# IMArduino-v1.net
KiCad netlist of a schematic drawn in EAGLE
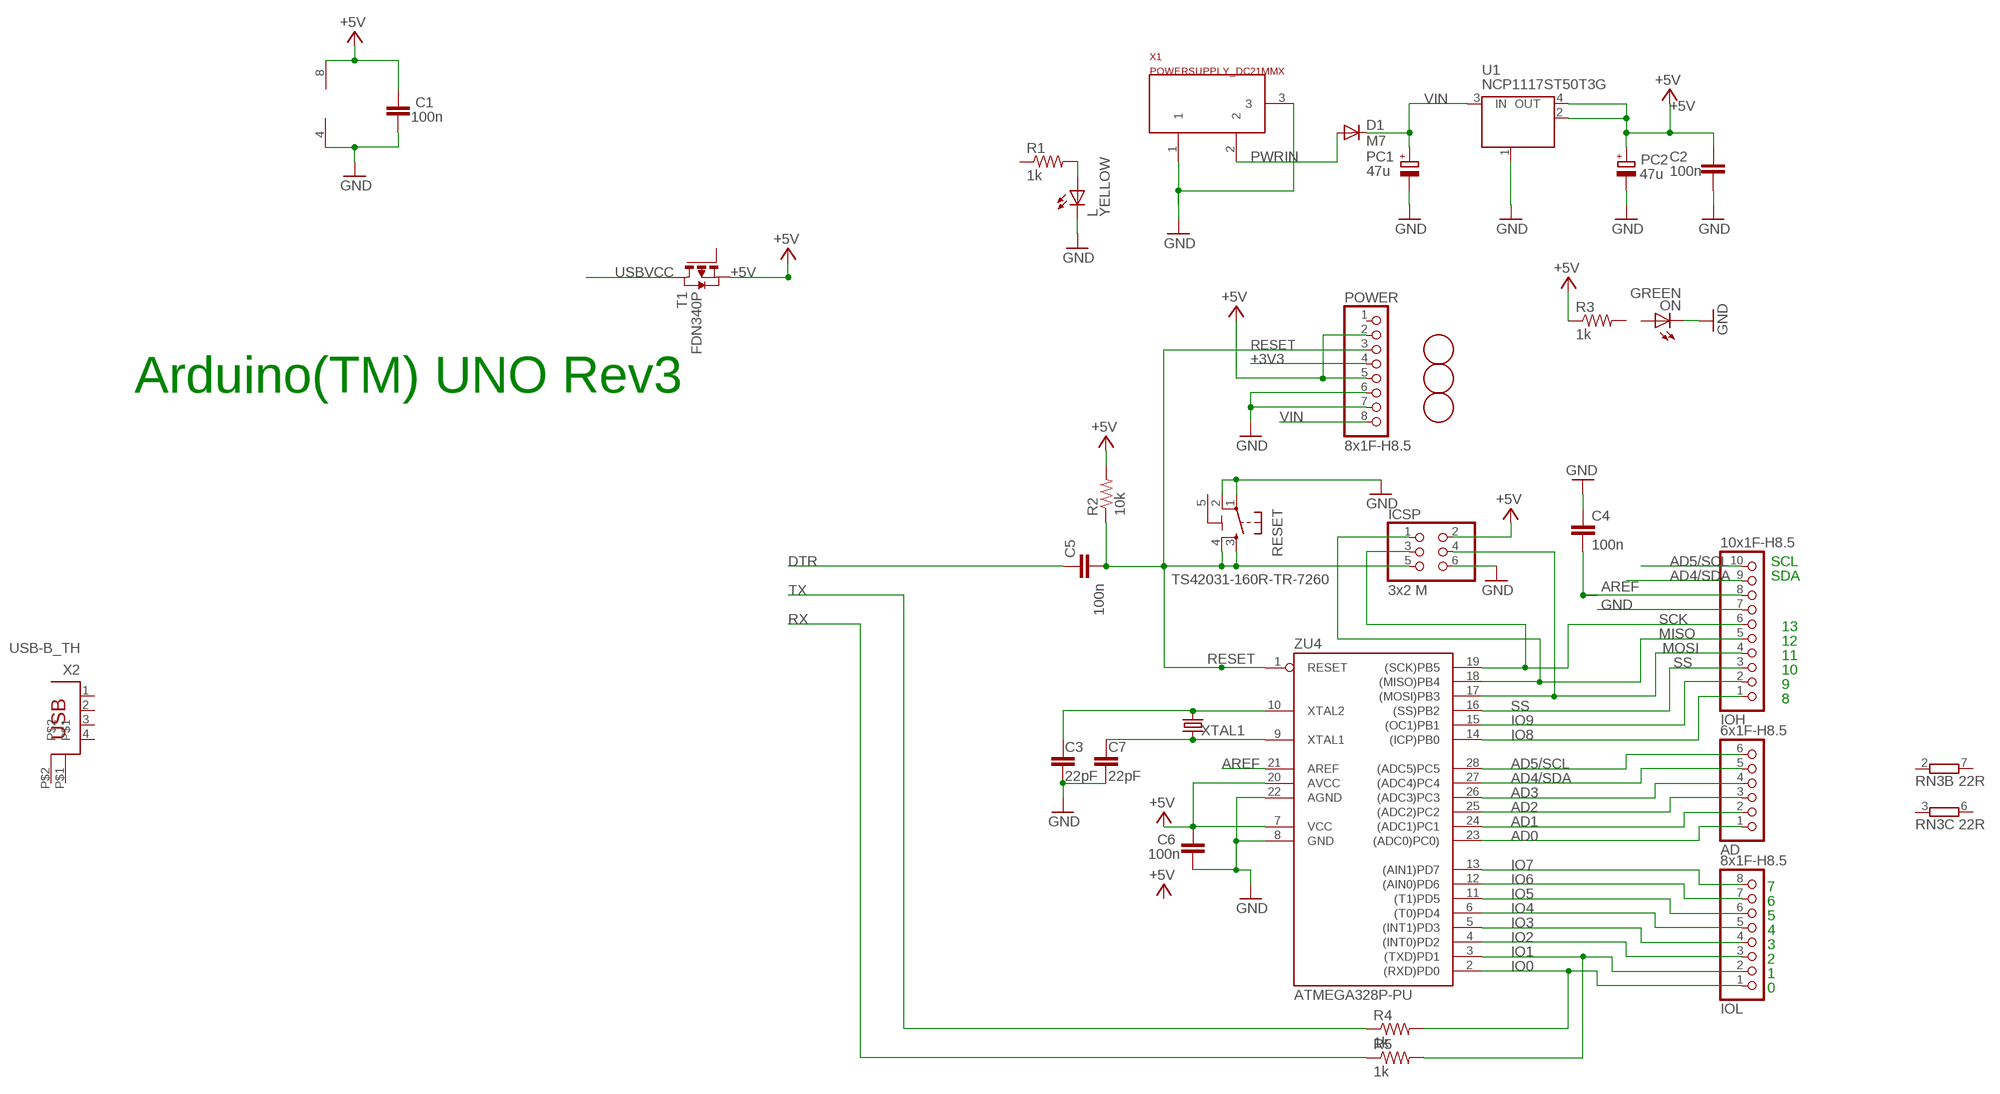
[diagram p0: schematic, sheet 1]

(export (version "E")
  (design (tool "Eeschema 10.0.6"))
  (components
    (comp (ref "AD")
      (value "6x1F-H8.5")
      (footprint "eagle-import:1X06")
      (libsource (lib "eagle-import") (part "PINHD-1X6"))
    )
    (comp (ref "C1")
      (value "100n")
      (footprint "eagle-import:C0603-ROUND")
      (libsource (lib "eagle-import") (part "C-EU0603-RND"))
    )
    (comp (ref "C2")
      (value "100n")
      (footprint "eagle-import:C0603-ROUND")
      (libsource (lib "eagle-import") (part "C-EU0603-RND"))
    )
    (comp (ref "C3")
      (value "22pF")
      (footprint "eagle-import:C0603-ROUND")
      (libsource (lib "eagle-import") (part "C-EU0603-RND"))
    )
    (comp (ref "C4")
      (value "100n")
      (footprint "eagle-import:C0603-ROUND")
      (libsource (lib "eagle-import") (part "C-EU0603-RND"))
    )
    (comp (ref "C5")
      (value "100n")
      (footprint "eagle-import:C0603-ROUND")
      (libsource (lib "eagle-import") (part "C-EU0603-RND"))
    )
    (comp (ref "C6")
      (value "100n")
      (footprint "eagle-import:C0603-ROUND")
      (libsource (lib "eagle-import") (part "C-EU0603-RND"))
    )
    (comp (ref "C7")
      (value "22pF")
      (footprint "eagle-import:C0603-ROUND")
      (libsource (lib "eagle-import") (part "C-EU0603-RND"))
    )
    (comp (ref "D1")
      (value "M7")
      (footprint "eagle-import:SMB")
      (libsource (lib "eagle-import") (part "DIODE-SMB"))
    )
    (comp (ref "FD1")
      (value "FIDUCIALMOUNT")
      (footprint "eagle-import:FIDUCIA-MOUNT")
      (libsource (lib "eagle-import") (part "FIDUCIALMOUNT"))
    )
    (comp (ref "FD2")
      (value "FIDUCIALMOUNT")
      (footprint "eagle-import:FIDUCIA-MOUNT")
      (libsource (lib "eagle-import") (part "FIDUCIALMOUNT"))
    )
    (comp (ref "FD3")
      (value "FIDUCIALMOUNT")
      (footprint "eagle-import:FIDUCIA-MOUNT")
      (libsource (lib "eagle-import") (part "FIDUCIALMOUNT"))
    )
    (comp (ref "ICSP")
      (value "3x2 M")
      (footprint "eagle-import:2X03")
      (libsource (lib "eagle-import") (part "PINHD-2X3"))
    )
    (comp (ref "IOH")
      (value "10x1F-H8.5")
      (footprint "eagle-import:1X10")
      (libsource (lib "eagle-import") (part "PINHD-1X10_ARD"))
    )
    (comp (ref "IOL")
      (value "8x1F-H8.5")
      (footprint "eagle-import:1X08")
      (libsource (lib "eagle-import") (part "PINHD-1X8"))
    )
    (comp (ref "L")
      (value "YELLOW")
      (footprint "eagle-import:CHIP-LED0805")
      (libsource (lib "eagle-import") (part "LEDCHIP-LED0805"))
    )
    (comp (ref "ON")
      (value "GREEN")
      (footprint "eagle-import:CHIP-LED0805")
      (libsource (lib "eagle-import") (part "LEDCHIP-LED0805"))
    )
    (comp (ref "PC1")
      (value "47u")
      (footprint "eagle-import:PANASONIC_D")
      (libsource (lib "eagle-import") (part "CPOL-EUD"))
    )
    (comp (ref "PC2")
      (value "47u")
      (footprint "eagle-import:PANASONIC_D")
      (libsource (lib "eagle-import") (part "CPOL-EUD"))
    )
    (comp (ref "POWER")
      (value "8x1F-H8.5")
      (footprint "eagle-import:1X08")
      (libsource (lib "eagle-import") (part "PINHD-1X8"))
    )
    (comp (ref "R1")
      (value "1k")
      (footprint "eagle-import:0204_7")
      (libsource (lib "eagle-import") (part "R-US_0204/7"))
    )
    (comp (ref "R2")
      (value "10k")
      (footprint "eagle-import:0204_7")
      (libsource (lib "eagle-import") (part "R-US_0204/7"))
    )
    (comp (ref "R3")
      (value "1k")
      (footprint "eagle-import:0204_7")
      (libsource (lib "eagle-import") (part "R-US_0204/7"))
    )
    (comp (ref "R4")
      (value "1k")
      (footprint "eagle-import:0204_7")
      (libsource (lib "eagle-import") (part "R-US_0204/7"))
    )
    (comp (ref "R5")
      (value "1k")
      (footprint "eagle-import:0204_7")
      (libsource (lib "eagle-import") (part "R-US_0204/7"))
    )
    (comp (ref "RESET")
      (value "TS42031-160R-TR-7260")
      (footprint "eagle-import:TS42")
      (libsource (lib "eagle-import") (part "TS42"))
    )
    (comp (ref "RN3")
      (value "22R")
      (footprint "eagle-import:CAY16")
      (libsource (lib "eagle-import") (part "4R-NCAY16"))
    )
    (comp (ref "T1")
      (value "FDN340P")
      (footprint "eagle-import:SOT-23")
      (libsource (lib "eagle-import") (part "PMOSSOT23"))
    )
    (comp (ref "U1")
      (value "NCP1117ST50T3G")
      (footprint "eagle-import:SOT223")
      (libsource (lib "eagle-import") (part "MC33269ST-3.3T3"))
    )
    (comp (ref "U5")
      (value "LMV358IDGKR")
      (footprint "eagle-import:MSOP08")
      (libsource (lib "eagle-import") (part "LMV358?MMX"))
    )
    (comp (ref "X1")
      (value "POWERSUPPLY_DC21MMX")
      (footprint "eagle-import:POWERSUPPLY_DC-21MM")
      (libsource (lib "eagle-import") (part "POWERSUPPLY_DC21MMX"))
    )
    (comp (ref "X2")
      (value "USB-B_TH")
      (footprint "eagle-import:PN61729")
      (libsource (lib "eagle-import") (part "PN61729"))
    )
    (comp (ref "XTAL1")
      (value "CRYSTALHC49U-V")
      (footprint "eagle-import:HC49U-V")
      (libsource (lib "eagle-import") (part "CRYSTALHC49U-V"))
    )
    (comp (ref "ZU4")
      (value "ATMEGA328P-PU")
      (footprint "eagle-import:DIL28-3")
      (libsource (lib "eagle-import") (part "ATMEGA328P-PU"))
    )
  )
  (nets
    (net (code "1") (name "+5V") (class "Default")
      (node (ref "C1") (pin "2") (pinfunction "2_2") (pintype "passive"))
      (node (ref "C2") (pin "2") (pinfunction "2_2") (pintype "passive"))
      (node (ref "C6") (pin "2") (pinfunction "2_2") (pintype "passive"))
      (node (ref "ICSP") (pin "2") (pinfunction "2_2") (pintype "passive"))
      (node (ref "PC2") (pin "+") (pinfunction "+_+") (pintype "passive"))
      (node (ref "POWER") (pin "2") (pinfunction "2_2") (pintype "passive"))
      (node (ref "POWER") (pin "5") (pinfunction "5_5") (pintype "passive"))
      (node (ref "R2") (pin "2") (pinfunction "2_2") (pintype "passive"))
      (node (ref "R3") (pin "1") (pinfunction "1_1") (pintype "passive"))
      (node (ref "T1") (pin "2") (pinfunction "S_2") (pintype "passive"))
      (node (ref "U1") (pin "2") (pinfunction "OUT_2") (pintype "passive"))
      (node (ref "U1") (pin "4") (pinfunction "OUT_4") (pintype "passive"))
      (node (ref "U5") (pin "8") (pinfunction "V+_8") (pintype "power_in"))
      (node (ref "ZU4") (pin "20") (pinfunction "AVCC_20") (pintype "power_in"))
      (node (ref "ZU4") (pin "7") (pinfunction "VCC_7") (pintype "power_in"))
    )
    (net (code "2") (name "/+3V3") (class "Default")
      (node (ref "POWER") (pin "4") (pinfunction "4_4") (pintype "passive"))
    )
    (net (code "3") (name "/5-GND") (class "Default")
      (node (ref "RESET") (pin "5") (pinfunction "5-GND_5") (pintype "power_in"))
    )
    (net (code "4") (name "/AD0") (class "Default")
      (node (ref "AD") (pin "1") (pinfunction "1_1") (pintype "passive"))
      (node (ref "ZU4") (pin "23") (pinfunction "(ADC0)PC0)_23") (pintype "bidirectional"))
    )
    (net (code "5") (name "/AD1") (class "Default")
      (node (ref "AD") (pin "2") (pinfunction "2_2") (pintype "passive"))
      (node (ref "ZU4") (pin "24") (pinfunction "(ADC1)PC1_24") (pintype "bidirectional"))
    )
    (net (code "6") (name "/AD2") (class "Default")
      (node (ref "AD") (pin "3") (pinfunction "3_3") (pintype "passive"))
      (node (ref "ZU4") (pin "25") (pinfunction "(ADC2)PC2_25") (pintype "bidirectional"))
    )
    (net (code "7") (name "/AD3") (class "Default")
      (node (ref "AD") (pin "4") (pinfunction "4_4") (pintype "passive"))
      (node (ref "ZU4") (pin "26") (pinfunction "(ADC3)PC3_26") (pintype "bidirectional"))
    )
    (net (code "8") (name "/AD4{slash}SDA") (class "Default")
      (node (ref "AD") (pin "5") (pinfunction "5_5") (pintype "passive"))
      (node (ref "IOH") (pin "9") (pinfunction "9_9") (pintype "passive"))
      (node (ref "ZU4") (pin "27") (pinfunction "(ADC4)PC4_27") (pintype "bidirectional"))
    )
    (net (code "9") (name "/AD5{slash}SCL") (class "Default")
      (node (ref "AD") (pin "6") (pinfunction "6_6") (pintype "passive"))
      (node (ref "IOH") (pin "10") (pinfunction "10_10") (pintype "passive"))
      (node (ref "ZU4") (pin "28") (pinfunction "(ADC5)PC5_28") (pintype "bidirectional"))
    )
    (net (code "10") (name "/AREF") (class "Default")
      (node (ref "C4") (pin "2") (pinfunction "2_2") (pintype "passive"))
      (node (ref "IOH") (pin "8") (pinfunction "8_8") (pintype "passive"))
      (node (ref "ZU4") (pin "21") (pinfunction "AREF_21") (pintype "passive"))
    )
    (net (code "11") (name "/DTR") (class "Default")
      (node (ref "C5") (pin "1") (pinfunction "1_1") (pintype "passive"))
    )
    (net (code "12") (name "/IO0") (class "Default")
      (node (ref "IOL") (pin "1") (pinfunction "1_1") (pintype "passive"))
      (node (ref "R4") (pin "2") (pinfunction "2_2") (pintype "passive"))
      (node (ref "ZU4") (pin "2") (pinfunction "(RXD)PD0_2") (pintype "bidirectional"))
    )
    (net (code "13") (name "/IO1") (class "Default")
      (node (ref "IOL") (pin "2") (pinfunction "2_2") (pintype "passive"))
      (node (ref "R5") (pin "2") (pinfunction "2_2") (pintype "passive"))
      (node (ref "ZU4") (pin "3") (pinfunction "(TXD)PD1_3") (pintype "bidirectional"))
    )
    (net (code "14") (name "/IO2") (class "Default")
      (node (ref "IOL") (pin "3") (pinfunction "3_3") (pintype "passive"))
      (node (ref "ZU4") (pin "4") (pinfunction "(INT0)PD2_4") (pintype "bidirectional"))
    )
    (net (code "15") (name "/IO3") (class "Default")
      (node (ref "IOL") (pin "4") (pinfunction "4_4") (pintype "passive"))
      (node (ref "ZU4") (pin "5") (pinfunction "(INT1)PD3_5") (pintype "bidirectional"))
    )
    (net (code "16") (name "/IO4") (class "Default")
      (node (ref "IOL") (pin "5") (pinfunction "5_5") (pintype "passive"))
      (node (ref "ZU4") (pin "6") (pinfunction "(T0)PD4_6") (pintype "bidirectional"))
    )
    (net (code "17") (name "/IO5") (class "Default")
      (node (ref "IOL") (pin "6") (pinfunction "6_6") (pintype "passive"))
      (node (ref "ZU4") (pin "11") (pinfunction "(T1)PD5_11") (pintype "bidirectional"))
    )
    (net (code "18") (name "/IO6") (class "Default")
      (node (ref "IOL") (pin "7") (pinfunction "7_7") (pintype "passive"))
      (node (ref "ZU4") (pin "12") (pinfunction "(AIN0)PD6_12") (pintype "bidirectional"))
    )
    (net (code "19") (name "/IO7") (class "Default")
      (node (ref "IOL") (pin "8") (pinfunction "8_8") (pintype "passive"))
      (node (ref "ZU4") (pin "13") (pinfunction "(AIN1)PD7_13") (pintype "bidirectional"))
    )
    (net (code "20") (name "/IO8") (class "Default")
      (node (ref "IOH") (pin "1") (pinfunction "1_1") (pintype "passive"))
      (node (ref "ZU4") (pin "14") (pinfunction "(ICP)PB0_14") (pintype "bidirectional"))
    )
    (net (code "21") (name "/IO9") (class "Default")
      (node (ref "IOH") (pin "2") (pinfunction "2_2") (pintype "passive"))
      (node (ref "ZU4") (pin "15") (pinfunction "(OC1)PB1_15") (pintype "bidirectional"))
    )
    (net (code "22") (name "/MISO") (class "Default")
      (node (ref "ICSP") (pin "1") (pinfunction "1_1") (pintype "passive"))
      (node (ref "IOH") (pin "5") (pinfunction "5_5") (pintype "passive"))
      (node (ref "ZU4") (pin "18") (pinfunction "(MISO)PB4_18") (pintype "bidirectional"))
    )
    (net (code "23") (name "/MOSI") (class "Default")
      (node (ref "ICSP") (pin "4") (pinfunction "4_4") (pintype "passive"))
      (node (ref "IOH") (pin "4") (pinfunction "4_4") (pintype "passive"))
      (node (ref "ZU4") (pin "17") (pinfunction "(MOSI)PB3_17") (pintype "bidirectional"))
    )
    (net (code "24") (name "/PWRIN") (class "Default")
      (node (ref "D1") (pin "A") (pinfunction "A_A") (pintype "passive"))
      (node (ref "X1") (pin "2") (pinfunction "2_2") (pintype "power_in"))
    )
    (net (code "25") (name "/RESET") (class "Default")
      (node (ref "C5") (pin "2") (pinfunction "2_2") (pintype "passive"))
      (node (ref "ICSP") (pin "5") (pinfunction "5_5") (pintype "passive"))
      (node (ref "POWER") (pin "3") (pinfunction "3_3") (pintype "passive"))
      (node (ref "R2") (pin "1") (pinfunction "1_1") (pintype "passive"))
      (node (ref "RESET") (pin "3") (pinfunction "3_3") (pintype "passive"))
      (node (ref "RESET") (pin "4") (pinfunction "4_4") (pintype "passive"))
      (node (ref "ZU4") (pin "1") (pinfunction "RESET_1") (pintype "input"))
    )
    (net (code "26") (name "/RX") (class "Default")
      (node (ref "R5") (pin "1") (pinfunction "1_1") (pintype "passive"))
    )
    (net (code "27") (name "/SCK") (class "Default")
      (node (ref "ICSP") (pin "3") (pinfunction "3_3") (pintype "passive"))
      (node (ref "IOH") (pin "6") (pinfunction "6_6") (pintype "passive"))
      (node (ref "ZU4") (pin "19") (pinfunction "(SCK)PB5_19") (pintype "bidirectional"))
    )
    (net (code "28") (name "/SS") (class "Default")
      (node (ref "IOH") (pin "3") (pinfunction "3_3") (pintype "passive"))
      (node (ref "ZU4") (pin "16") (pinfunction "(SS)PB2_16") (pintype "bidirectional"))
    )
    (net (code "29") (name "/TX") (class "Default")
      (node (ref "R4") (pin "1") (pinfunction "1_1") (pintype "passive"))
    )
    (net (code "30") (name "/USBVCC") (class "Default")
      (node (ref "T1") (pin "1") (pinfunction "D_1") (pintype "passive"))
    )
    (net (code "31") (name "/VIN") (class "Default")
      (node (ref "D1") (pin "C") (pinfunction "C_C") (pintype "passive"))
      (node (ref "PC1") (pin "+") (pinfunction "+_+") (pintype "passive"))
      (node (ref "POWER") (pin "8") (pinfunction "8_8") (pintype "passive"))
      (node (ref "U1") (pin "3") (pinfunction "IN_3") (pintype "input"))
    )
    (net (code "32") (name "GND") (class "Default")
      (node (ref "C1") (pin "1") (pinfunction "1_1") (pintype "passive"))
      (node (ref "C2") (pin "1") (pinfunction "1_1") (pintype "passive"))
      (node (ref "C3") (pin "1") (pinfunction "1_1") (pintype "passive"))
      (node (ref "C4") (pin "1") (pinfunction "1_1") (pintype "passive"))
      (node (ref "C6") (pin "1") (pinfunction "1_1") (pintype "passive"))
      (node (ref "C7") (pin "1") (pinfunction "1_1") (pintype "passive"))
      (node (ref "ICSP") (pin "6") (pinfunction "6_6") (pintype "passive"))
      (node (ref "IOH") (pin "7") (pinfunction "7_7") (pintype "passive"))
      (node (ref "L") (pin "C") (pinfunction "C_C") (pintype "passive"))
      (node (ref "ON") (pin "C") (pinfunction "C_C") (pintype "passive"))
      (node (ref "PC1") (pin "-") (pinfunction "-_-") (pintype "passive"))
      (node (ref "PC2") (pin "-") (pinfunction "-_-") (pintype "passive"))
      (node (ref "POWER") (pin "6") (pinfunction "6_6") (pintype "passive"))
      (node (ref "POWER") (pin "7") (pinfunction "7_7") (pintype "passive"))
      (node (ref "RESET") (pin "1") (pinfunction "1_1") (pintype "passive"))
      (node (ref "RESET") (pin "2") (pinfunction "2_2") (pintype "passive"))
      (node (ref "U1") (pin "1") (pinfunction "GND/ADJ_1") (pintype "input"))
      (node (ref "U5") (pin "4") (pinfunction "V-_4") (pintype "power_in"))
      (node (ref "X1") (pin "1") (pinfunction "1_1") (pintype "power_in"))
      (node (ref "X1") (pin "3") (pinfunction "3_3") (pintype "power_in"))
      (node (ref "ZU4") (pin "22") (pinfunction "AGND_22") (pintype "power_in"))
      (node (ref "ZU4") (pin "8") (pinfunction "GND_8") (pintype "power_in"))
    )
    (net (code "33") (name "Net-(L-PadA)") (class "Default")
      (node (ref "L") (pin "A") (pinfunction "A_A") (pintype "passive"))
      (node (ref "R1") (pin "2") (pinfunction "2_2") (pintype "passive"))
    )
    (net (code "34") (name "Net-(ZU4-XTAL1)") (class "Default")
      (node (ref "C7") (pin "2") (pinfunction "2_2") (pintype "passive"))
      (node (ref "XTAL1") (pin "1") (pinfunction "1_1") (pintype "passive"))
      (node (ref "ZU4") (pin "9") (pinfunction "XTAL1_9") (pintype "bidirectional"))
    )
    (net (code "35") (name "Net-(ZU4-XTAL2)") (class "Default")
      (node (ref "C3") (pin "2") (pinfunction "2_2") (pintype "passive"))
      (node (ref "XTAL1") (pin "2") (pinfunction "2_2") (pintype "passive"))
      (node (ref "ZU4") (pin "10") (pinfunction "XTAL2_10") (pintype "bidirectional"))
    )
    (net (code "36") (name "unconnected-(ON-PadA)") (class "Default")
      (node (ref "ON") (pin "A") (pinfunction "A_A") (pintype "passive"))
    )
    (net (code "37") (name "unconnected-(POWER-Pad1)") (class "Default")
      (node (ref "POWER") (pin "1") (pinfunction "1_1") (pintype "passive"))
    )
    (net (code "38") (name "unconnected-(R1-Pad1)") (class "Default")
      (node (ref "R1") (pin "1") (pinfunction "1_1") (pintype "passive"))
    )
    (net (code "39") (name "unconnected-(R3-Pad2)") (class "Default")
      (node (ref "R3") (pin "2") (pinfunction "2_2") (pintype "passive"))
    )
    (net (code "40") (name "unconnected-(RN3B-1-Pad2)") (class "Default")
      (node (ref "RN3") (pin "2") (pinfunction "1_2") (pintype "passive"))
    )
    (net (code "41") (name "unconnected-(RN3B-2-Pad7)") (class "Default")
      (node (ref "RN3") (pin "7") (pinfunction "2_7") (pintype "passive"))
    )
    (net (code "42") (name "unconnected-(RN3C-1-Pad3)") (class "Default")
      (node (ref "RN3") (pin "3") (pinfunction "1_3") (pintype "passive"))
    )
    (net (code "43") (name "unconnected-(RN3C-2-Pad6)") (class "Default")
      (node (ref "RN3") (pin "6") (pinfunction "2_6") (pintype "passive"))
    )
    (net (code "44") (name "unconnected-(T1-G-Pad3)") (class "Default")
      (node (ref "T1") (pin "3") (pinfunction "G_3") (pintype "passive"))
    )
    (net (code "45") (name "unconnected-(X2-Pad1)") (class "Default")
      (node (ref "X2") (pin "1") (pinfunction "1_1") (pintype "bidirectional"))
    )
    (net (code "46") (name "unconnected-(X2-Pad2)") (class "Default")
      (node (ref "X2") (pin "2") (pinfunction "2_2") (pintype "bidirectional"))
    )
    (net (code "47") (name "unconnected-(X2-Pad3)") (class "Default")
      (node (ref "X2") (pin "3") (pinfunction "3_3") (pintype "bidirectional"))
    )
    (net (code "48") (name "unconnected-(X2-Pad4)") (class "Default")
      (node (ref "X2") (pin "4") (pinfunction "4_4") (pintype "bidirectional"))
    )
    (net (code "49") (name "unconnected-(X2-PadP$1)") (class "Default")
      (node (ref "X2") (pin "P$1") (pinfunction "P$1_P$1") (pintype "bidirectional"))
    )
    (net (code "50") (name "unconnected-(X2-PadP$2)") (class "Default")
      (node (ref "X2") (pin "P$2") (pinfunction "P$2_P$2") (pintype "bidirectional"))
    )
  )
)
